# rpi-ledarray-eagle.net
KiCad netlist of a schematic drawn in EAGLE
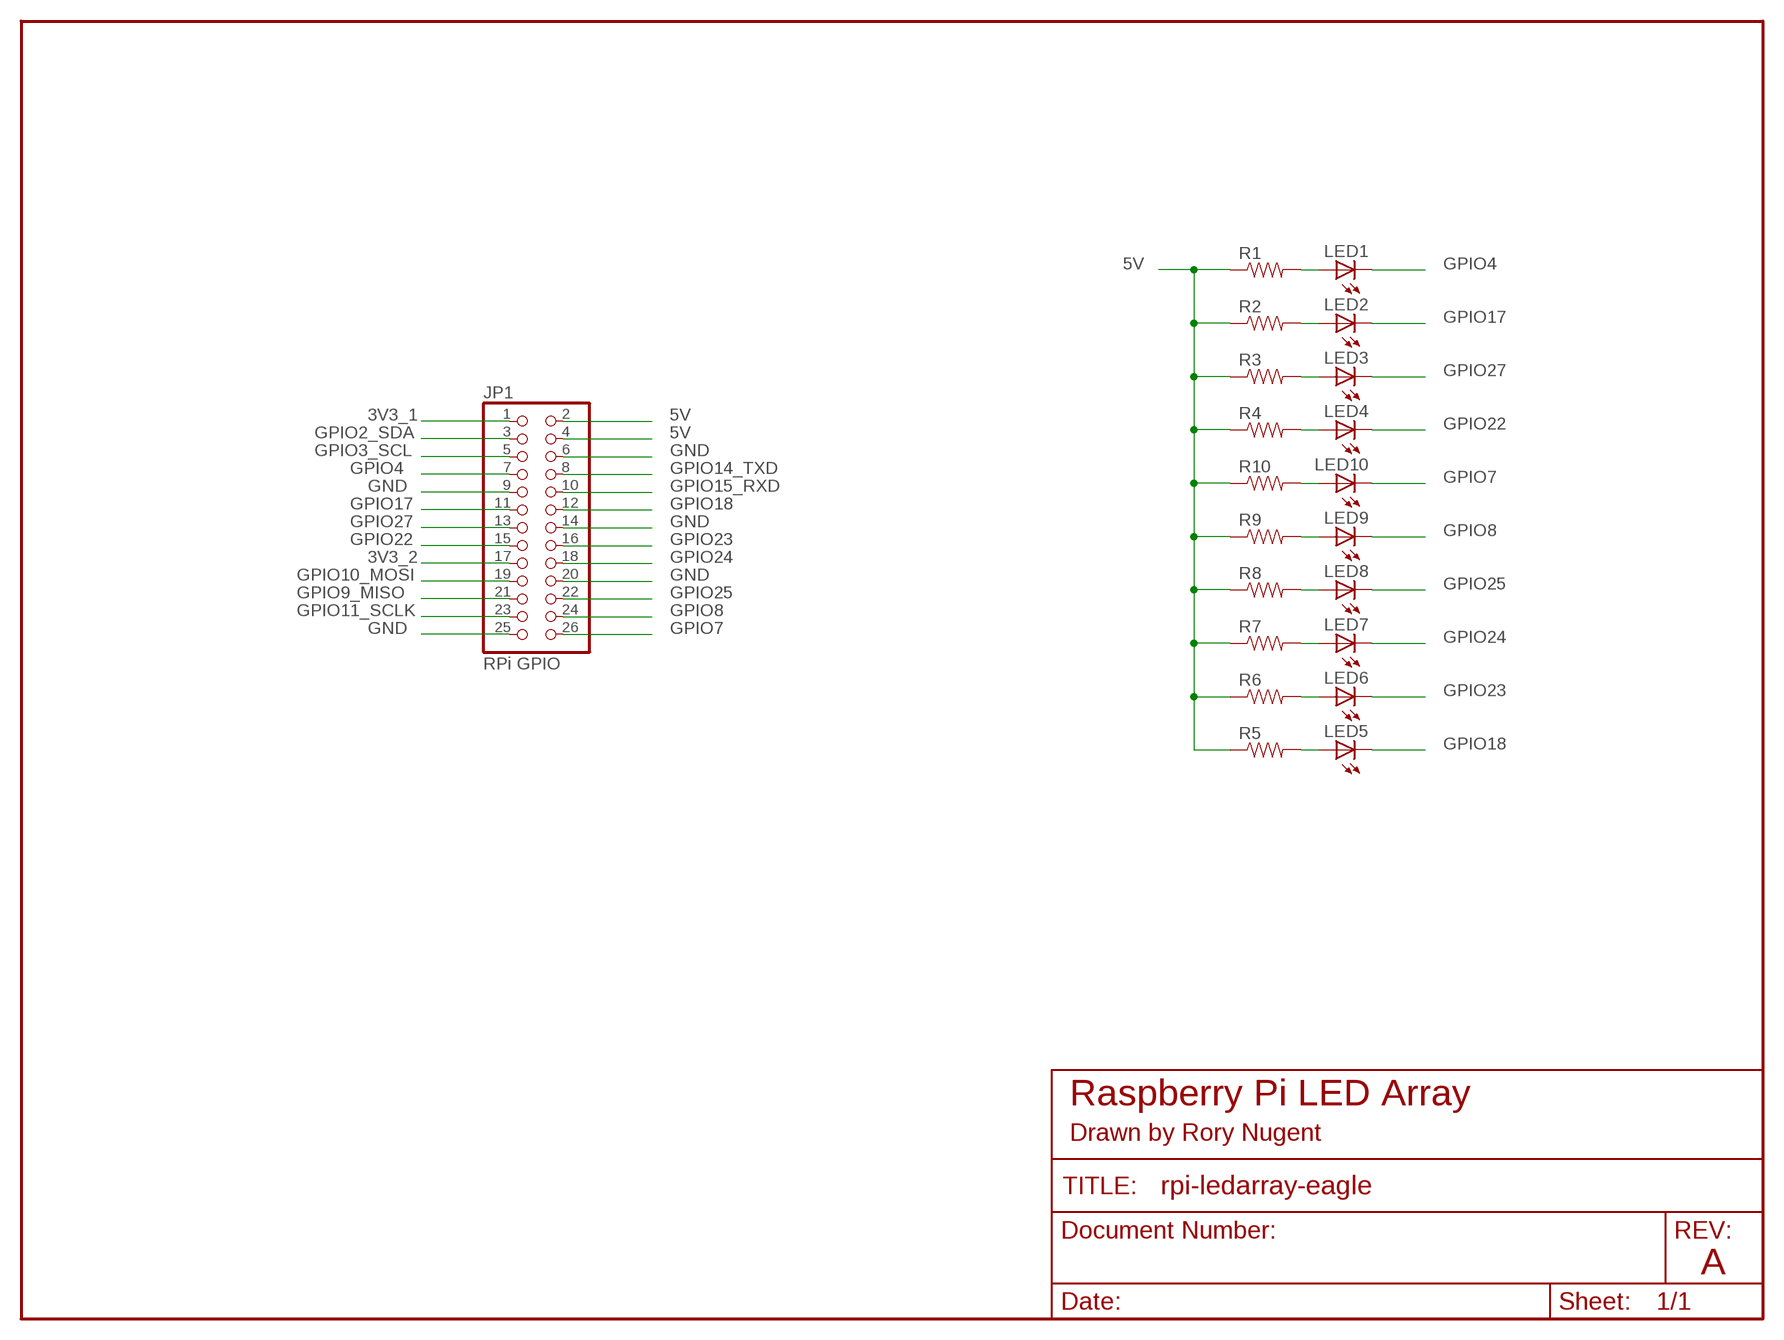
[diagram p0: schematic, sheet 1]

(export (version "E")
  (design (tool "Eeschema 10.0.6"))
  (components
    (comp (ref "JP1")
      (value "RPi GPIO")
      (footprint "eagle-import:2X13")
      (libsource (lib "eagle-import") (part "PINHD-2X13"))
    )
    (comp (ref "LED1")
      (value "LED1206")
      (footprint "eagle-import:LED-1206")
      (libsource (lib "eagle-import") (part "LED1206"))
    )
    (comp (ref "LED2")
      (value "LED1206")
      (footprint "eagle-import:LED-1206")
      (libsource (lib "eagle-import") (part "LED1206"))
    )
    (comp (ref "LED3")
      (value "LED1206")
      (footprint "eagle-import:LED-1206")
      (libsource (lib "eagle-import") (part "LED1206"))
    )
    (comp (ref "LED4")
      (value "LED1206")
      (footprint "eagle-import:LED-1206")
      (libsource (lib "eagle-import") (part "LED1206"))
    )
    (comp (ref "LED5")
      (value "LED1206")
      (footprint "eagle-import:LED-1206")
      (libsource (lib "eagle-import") (part "LED1206"))
    )
    (comp (ref "LED6")
      (value "LED1206")
      (footprint "eagle-import:LED-1206")
      (libsource (lib "eagle-import") (part "LED1206"))
    )
    (comp (ref "LED7")
      (value "LED1206")
      (footprint "eagle-import:LED-1206")
      (libsource (lib "eagle-import") (part "LED1206"))
    )
    (comp (ref "LED8")
      (value "LED1206")
      (footprint "eagle-import:LED-1206")
      (libsource (lib "eagle-import") (part "LED1206"))
    )
    (comp (ref "LED9")
      (value "LED1206")
      (footprint "eagle-import:LED-1206")
      (libsource (lib "eagle-import") (part "LED1206"))
    )
    (comp (ref "LED10")
      (value "LED1206")
      (footprint "eagle-import:LED-1206")
      (libsource (lib "eagle-import") (part "LED1206"))
    )
    (comp (ref "R1")
      (value "RESISTOR0603-RES")
      (footprint "eagle-import:0603-RES")
      (libsource (lib "eagle-import") (part "RESISTOR0603-RES"))
    )
    (comp (ref "R2")
      (value "RESISTOR0603-RES")
      (footprint "eagle-import:0603-RES")
      (libsource (lib "eagle-import") (part "RESISTOR0603-RES"))
    )
    (comp (ref "R3")
      (value "RESISTOR0603-RES")
      (footprint "eagle-import:0603-RES")
      (libsource (lib "eagle-import") (part "RESISTOR0603-RES"))
    )
    (comp (ref "R4")
      (value "RESISTOR0603-RES")
      (footprint "eagle-import:0603-RES")
      (libsource (lib "eagle-import") (part "RESISTOR0603-RES"))
    )
    (comp (ref "R5")
      (value "RESISTOR0603-RES")
      (footprint "eagle-import:0603-RES")
      (libsource (lib "eagle-import") (part "RESISTOR0603-RES"))
    )
    (comp (ref "R6")
      (value "RESISTOR0603-RES")
      (footprint "eagle-import:0603-RES")
      (libsource (lib "eagle-import") (part "RESISTOR0603-RES"))
    )
    (comp (ref "R7")
      (value "RESISTOR0603-RES")
      (footprint "eagle-import:0603-RES")
      (libsource (lib "eagle-import") (part "RESISTOR0603-RES"))
    )
    (comp (ref "R8")
      (value "RESISTOR0603-RES")
      (footprint "eagle-import:0603-RES")
      (libsource (lib "eagle-import") (part "RESISTOR0603-RES"))
    )
    (comp (ref "R9")
      (value "RESISTOR0603-RES")
      (footprint "eagle-import:0603-RES")
      (libsource (lib "eagle-import") (part "RESISTOR0603-RES"))
    )
    (comp (ref "R10")
      (value "RESISTOR0603-RES")
      (footprint "eagle-import:0603-RES")
      (libsource (lib "eagle-import") (part "RESISTOR0603-RES"))
    )
  )
  (nets
    (net (code "1") (name "/3V3_1") (class "Default")
      (node (ref "JP1") (pin "1") (pinfunction "1_1") (pintype "passive"))
    )
    (net (code "2") (name "/3V3_2") (class "Default")
      (node (ref "JP1") (pin "17") (pinfunction "17_17") (pintype "passive"))
    )
    (net (code "3") (name "/5V") (class "Default")
      (node (ref "JP1") (pin "2") (pinfunction "2_2") (pintype "passive"))
      (node (ref "JP1") (pin "4") (pinfunction "4_4") (pintype "passive"))
      (node (ref "R1") (pin "1") (pinfunction "1_1") (pintype "passive"))
      (node (ref "R10") (pin "1") (pinfunction "1_1") (pintype "passive"))
      (node (ref "R2") (pin "1") (pinfunction "1_1") (pintype "passive"))
      (node (ref "R3") (pin "1") (pinfunction "1_1") (pintype "passive"))
      (node (ref "R4") (pin "1") (pinfunction "1_1") (pintype "passive"))
      (node (ref "R5") (pin "1") (pinfunction "1_1") (pintype "passive"))
      (node (ref "R6") (pin "1") (pinfunction "1_1") (pintype "passive"))
      (node (ref "R7") (pin "1") (pinfunction "1_1") (pintype "passive"))
      (node (ref "R8") (pin "1") (pinfunction "1_1") (pintype "passive"))
      (node (ref "R9") (pin "1") (pinfunction "1_1") (pintype "passive"))
    )
    (net (code "4") (name "/GND") (class "Default")
      (node (ref "JP1") (pin "14") (pinfunction "14_14") (pintype "passive"))
      (node (ref "JP1") (pin "20") (pinfunction "20_20") (pintype "passive"))
      (node (ref "JP1") (pin "25") (pinfunction "25_25") (pintype "passive"))
      (node (ref "JP1") (pin "6") (pinfunction "6_6") (pintype "passive"))
      (node (ref "JP1") (pin "9") (pinfunction "9_9") (pintype "passive"))
    )
    (net (code "5") (name "/GPIO2_SDA") (class "Default")
      (node (ref "JP1") (pin "3") (pinfunction "3_3") (pintype "passive"))
    )
    (net (code "6") (name "/GPIO3_SCL") (class "Default")
      (node (ref "JP1") (pin "5") (pinfunction "5_5") (pintype "passive"))
    )
    (net (code "7") (name "/GPIO4") (class "Default")
      (node (ref "JP1") (pin "7") (pinfunction "7_7") (pintype "passive"))
      (node (ref "LED1") (pin "C") (pinfunction "C_C") (pintype "passive"))
    )
    (net (code "8") (name "/GPIO7") (class "Default")
      (node (ref "JP1") (pin "26") (pinfunction "26_26") (pintype "passive"))
      (node (ref "LED10") (pin "C") (pinfunction "C_C") (pintype "passive"))
    )
    (net (code "9") (name "/GPIO8") (class "Default")
      (node (ref "JP1") (pin "24") (pinfunction "24_24") (pintype "passive"))
      (node (ref "LED9") (pin "C") (pinfunction "C_C") (pintype "passive"))
    )
    (net (code "10") (name "/GPIO9_MISO") (class "Default")
      (node (ref "JP1") (pin "21") (pinfunction "21_21") (pintype "passive"))
    )
    (net (code "11") (name "/GPIO10_MOSI") (class "Default")
      (node (ref "JP1") (pin "19") (pinfunction "19_19") (pintype "passive"))
    )
    (net (code "12") (name "/GPIO11_SCLK") (class "Default")
      (node (ref "JP1") (pin "23") (pinfunction "23_23") (pintype "passive"))
    )
    (net (code "13") (name "/GPIO14_TXD") (class "Default")
      (node (ref "JP1") (pin "8") (pinfunction "8_8") (pintype "passive"))
    )
    (net (code "14") (name "/GPIO15_RXD") (class "Default")
      (node (ref "JP1") (pin "10") (pinfunction "10_10") (pintype "passive"))
    )
    (net (code "15") (name "/GPIO17") (class "Default")
      (node (ref "JP1") (pin "11") (pinfunction "11_11") (pintype "passive"))
      (node (ref "LED2") (pin "C") (pinfunction "C_C") (pintype "passive"))
    )
    (net (code "16") (name "/GPIO18") (class "Default")
      (node (ref "JP1") (pin "12") (pinfunction "12_12") (pintype "passive"))
      (node (ref "LED5") (pin "C") (pinfunction "C_C") (pintype "passive"))
    )
    (net (code "17") (name "/GPIO22") (class "Default")
      (node (ref "JP1") (pin "15") (pinfunction "15_15") (pintype "passive"))
      (node (ref "LED4") (pin "C") (pinfunction "C_C") (pintype "passive"))
    )
    (net (code "18") (name "/GPIO23") (class "Default")
      (node (ref "JP1") (pin "16") (pinfunction "16_16") (pintype "passive"))
      (node (ref "LED6") (pin "C") (pinfunction "C_C") (pintype "passive"))
    )
    (net (code "19") (name "/GPIO24") (class "Default")
      (node (ref "JP1") (pin "18") (pinfunction "18_18") (pintype "passive"))
      (node (ref "LED7") (pin "C") (pinfunction "C_C") (pintype "passive"))
    )
    (net (code "20") (name "/GPIO25") (class "Default")
      (node (ref "JP1") (pin "22") (pinfunction "22_22") (pintype "passive"))
      (node (ref "LED8") (pin "C") (pinfunction "C_C") (pintype "passive"))
    )
    (net (code "21") (name "/GPIO27") (class "Default")
      (node (ref "JP1") (pin "13") (pinfunction "13_13") (pintype "passive"))
      (node (ref "LED3") (pin "C") (pinfunction "C_C") (pintype "passive"))
    )
    (net (code "22") (name "Net-(LED1-PadA)") (class "Default")
      (node (ref "LED1") (pin "A") (pinfunction "A_A") (pintype "passive"))
      (node (ref "R1") (pin "2") (pinfunction "2_2") (pintype "passive"))
    )
    (net (code "23") (name "Net-(LED2-PadA)") (class "Default")
      (node (ref "LED2") (pin "A") (pinfunction "A_A") (pintype "passive"))
      (node (ref "R2") (pin "2") (pinfunction "2_2") (pintype "passive"))
    )
    (net (code "24") (name "Net-(LED3-PadA)") (class "Default")
      (node (ref "LED3") (pin "A") (pinfunction "A_A") (pintype "passive"))
      (node (ref "R3") (pin "2") (pinfunction "2_2") (pintype "passive"))
    )
    (net (code "25") (name "Net-(LED4-PadA)") (class "Default")
      (node (ref "LED4") (pin "A") (pinfunction "A_A") (pintype "passive"))
      (node (ref "R4") (pin "2") (pinfunction "2_2") (pintype "passive"))
    )
    (net (code "26") (name "Net-(LED5-PadA)") (class "Default")
      (node (ref "LED5") (pin "A") (pinfunction "A_A") (pintype "passive"))
      (node (ref "R5") (pin "2") (pinfunction "2_2") (pintype "passive"))
    )
    (net (code "27") (name "Net-(LED6-PadA)") (class "Default")
      (node (ref "LED6") (pin "A") (pinfunction "A_A") (pintype "passive"))
      (node (ref "R6") (pin "2") (pinfunction "2_2") (pintype "passive"))
    )
    (net (code "28") (name "Net-(LED7-PadA)") (class "Default")
      (node (ref "LED7") (pin "A") (pinfunction "A_A") (pintype "passive"))
      (node (ref "R7") (pin "2") (pinfunction "2_2") (pintype "passive"))
    )
    (net (code "29") (name "Net-(LED8-PadA)") (class "Default")
      (node (ref "LED8") (pin "A") (pinfunction "A_A") (pintype "passive"))
      (node (ref "R8") (pin "2") (pinfunction "2_2") (pintype "passive"))
    )
    (net (code "30") (name "Net-(LED9-PadA)") (class "Default")
      (node (ref "LED9") (pin "A") (pinfunction "A_A") (pintype "passive"))
      (node (ref "R9") (pin "2") (pinfunction "2_2") (pintype "passive"))
    )
    (net (code "31") (name "Net-(LED10-PadA)") (class "Default")
      (node (ref "LED10") (pin "A") (pinfunction "A_A") (pintype "passive"))
      (node (ref "R10") (pin "2") (pinfunction "2_2") (pintype "passive"))
    )
  )
)
